# SLogger.net
KiCad netlist of a schematic drawn in EAGLE
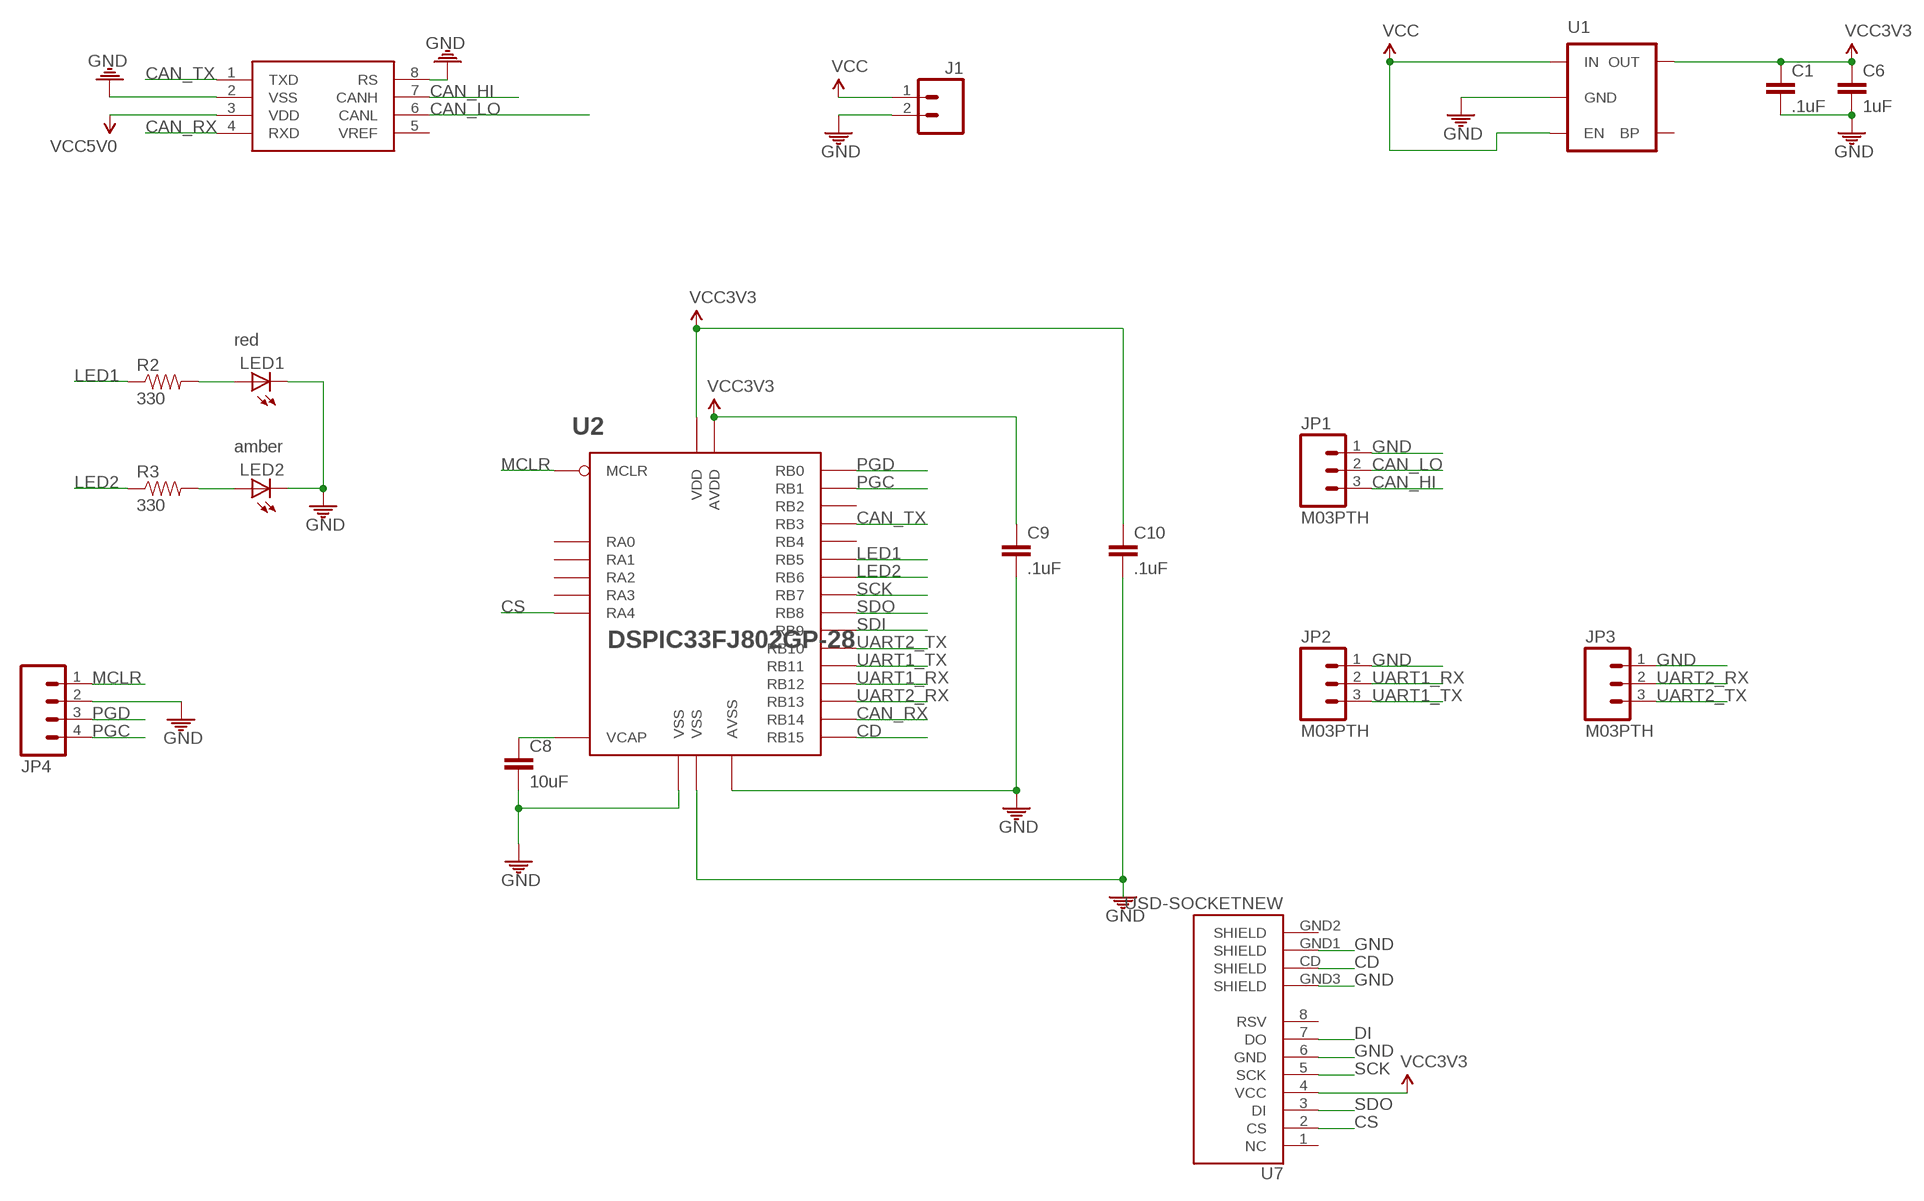
[diagram p0: schematic, sheet 1]

(export (version "E")
  (design (tool "Eeschema 10.0.6"))
  (components
    (comp (ref "C1")
      (value ".1uF")
      (footprint "eagle-import:0805")
      (libsource (lib "eagle-import") (part "CAP0805"))
    )
    (comp (ref "C6")
      (value "1uF")
      (footprint "eagle-import:0805")
      (libsource (lib "eagle-import") (part "CAP0805"))
    )
    (comp (ref "C8")
      (value "10uF")
      (footprint "eagle-import:0805")
      (libsource (lib "eagle-import") (part "CAP0805"))
    )
    (comp (ref "C9")
      (value ".1uF")
      (footprint "eagle-import:0805")
      (libsource (lib "eagle-import") (part "CAP0805"))
    )
    (comp (ref "C10")
      (value ".1uF")
      (footprint "eagle-import:0805")
      (libsource (lib "eagle-import") (part "CAP0805"))
    )
    (comp (ref "J1")
      (value "M02PTH")
      (footprint "eagle-import:1X02")
      (libsource (lib "eagle-import") (part "M02PTH"))
    )
    (comp (ref "JP1")
      (value "M03PTH")
      (footprint "eagle-import:1X03")
      (libsource (lib "eagle-import") (part "M03PTH"))
    )
    (comp (ref "JP2")
      (value "M03PTH")
      (footprint "eagle-import:1X03")
      (libsource (lib "eagle-import") (part "M03PTH"))
    )
    (comp (ref "JP3")
      (value "M03PTH")
      (footprint "eagle-import:1X03")
      (libsource (lib "eagle-import") (part "M03PTH"))
    )
    (comp (ref "JP4")
      (value "M04PTH")
      (footprint "eagle-import:1X04")
      (libsource (lib "eagle-import") (part "M04PTH"))
    )
    (comp (ref "LED1")
      (value "LED0805")
      (footprint "eagle-import:LED-0805")
      (fields (field (name "COLOR") "red"))
      (libsource (lib "eagle-import") (part "LED0805"))
    )
    (comp (ref "LED2")
      (value "LED0805")
      (footprint "eagle-import:LED-0805")
      (fields (field (name "COLOR") "amber"))
      (libsource (lib "eagle-import") (part "LED0805"))
    )
    (comp (ref "R2")
      (value "330")
      (footprint "eagle-import:0805")
      (libsource (lib "eagle-import") (part "RESISTOR0805-RES"))
    )
    (comp (ref "R3")
      (value "330")
      (footprint "eagle-import:0805")
      (libsource (lib "eagle-import") (part "RESISTOR0805-RES"))
    )
    (comp (ref "U1")
      (value "MIC52053.3V")
      (footprint "eagle-import:SOT23-5")
      (libsource (lib "eagle-import") (part "MIC52053.3V"))
    )
    (comp (ref "U2")
      (value "DSPIC33FJ802GP-28")
      (footprint "eagle-import:SOIC28-W")
      (libsource (lib "eagle-import") (part "DSPIC33FJ802GP-28"))
    )
    (comp (ref "U4")
      (value "MCP2551")
      (footprint "eagle-import:SO08")
      (libsource (lib "eagle-import") (part "MCP2551"))
    )
    (comp (ref "U7")
      (value "USD-SOCKETNEW")
      (footprint "eagle-import:MICRO-SD-SOCKET-PP")
      (libsource (lib "eagle-import") (part "USD-SOCKETNEW"))
    )
  )
  (nets
    (net (code "1") (name "/CAN_HI") (class "Default")
      (node (ref "JP1") (pin "3") (pinfunction "3_3") (pintype "passive"))
      (node (ref "U4") (pin "7") (pinfunction "CANH_7") (pintype "bidirectional"))
    )
    (net (code "2") (name "/CAN_LO") (class "Default")
      (node (ref "JP1") (pin "2") (pinfunction "2_2") (pintype "passive"))
      (node (ref "U4") (pin "6") (pinfunction "CANL_6") (pintype "bidirectional"))
    )
    (net (code "3") (name "/CAN_RX") (class "Default")
      (node (ref "U2") (pin "P$25") (pinfunction "RB14_P$25") (pintype "bidirectional"))
      (node (ref "U4") (pin "4") (pinfunction "RXD_4") (pintype "bidirectional"))
    )
    (net (code "4") (name "/CAN_TX") (class "Default")
      (node (ref "U2") (pin "P$7") (pinfunction "RB3_P$7") (pintype "bidirectional"))
      (node (ref "U4") (pin "1") (pinfunction "TXD_1") (pintype "bidirectional"))
    )
    (net (code "5") (name "/CD") (class "Default")
      (node (ref "U2") (pin "P$26") (pinfunction "RB15_P$26") (pintype "bidirectional"))
      (node (ref "U7") (pin "CD") (pinfunction "SHIELD_CD") (pintype "bidirectional"))
    )
    (net (code "6") (name "/CS") (class "Default")
      (node (ref "U2") (pin "P$12") (pinfunction "RA4_P$12") (pintype "bidirectional"))
      (node (ref "U7") (pin "2") (pinfunction "CS_2") (pintype "bidirectional"))
    )
    (net (code "7") (name "/DI") (class "Default")
      (node (ref "U7") (pin "7") (pinfunction "DO_7") (pintype "bidirectional"))
    )
    (net (code "8") (name "/LED1") (class "Default")
      (node (ref "R2") (pin "1") (pinfunction "1_1") (pintype "passive"))
      (node (ref "U2") (pin "P$14") (pinfunction "RB5_P$14") (pintype "bidirectional"))
    )
    (net (code "9") (name "/LED2") (class "Default")
      (node (ref "R3") (pin "1") (pinfunction "1_1") (pintype "passive"))
      (node (ref "U2") (pin "P$15") (pinfunction "RB6_P$15") (pintype "bidirectional"))
    )
    (net (code "10") (name "/MCLR") (class "Default")
      (node (ref "JP4") (pin "1") (pinfunction "1_1") (pintype "passive"))
      (node (ref "U2") (pin "P$1") (pinfunction "MCLR_P$1") (pintype "bidirectional"))
    )
    (net (code "11") (name "/PGC") (class "Default")
      (node (ref "JP4") (pin "4") (pinfunction "4_4") (pintype "passive"))
      (node (ref "U2") (pin "P$5") (pinfunction "RB1_P$5") (pintype "bidirectional"))
    )
    (net (code "12") (name "/PGD") (class "Default")
      (node (ref "JP4") (pin "3") (pinfunction "3_3") (pintype "passive"))
      (node (ref "U2") (pin "P$4") (pinfunction "RB0_P$4") (pintype "bidirectional"))
    )
    (net (code "13") (name "/SCK") (class "Default")
      (node (ref "U2") (pin "P$16") (pinfunction "RB7_P$16") (pintype "bidirectional"))
      (node (ref "U7") (pin "5") (pinfunction "SCK_5") (pintype "bidirectional"))
    )
    (net (code "14") (name "/SDI") (class "Default")
      (node (ref "U2") (pin "P$18") (pinfunction "RB9_P$18") (pintype "bidirectional"))
    )
    (net (code "15") (name "/SDO") (class "Default")
      (node (ref "U2") (pin "P$17") (pinfunction "RB8_P$17") (pintype "bidirectional"))
      (node (ref "U7") (pin "3") (pinfunction "DI_3") (pintype "bidirectional"))
    )
    (net (code "16") (name "/UART1_RX") (class "Default")
      (node (ref "JP2") (pin "2") (pinfunction "2_2") (pintype "passive"))
      (node (ref "U2") (pin "P$23") (pinfunction "RB12_P$23") (pintype "bidirectional"))
    )
    (net (code "17") (name "/UART1_TX") (class "Default")
      (node (ref "JP2") (pin "3") (pinfunction "3_3") (pintype "passive"))
      (node (ref "U2") (pin "P$22") (pinfunction "RB11_P$22") (pintype "bidirectional"))
    )
    (net (code "18") (name "/UART2_RX") (class "Default")
      (node (ref "JP3") (pin "2") (pinfunction "2_2") (pintype "passive"))
      (node (ref "U2") (pin "P$24") (pinfunction "RB13_P$24") (pintype "bidirectional"))
    )
    (net (code "19") (name "/UART2_TX") (class "Default")
      (node (ref "JP3") (pin "3") (pinfunction "3_3") (pintype "passive"))
      (node (ref "U2") (pin "P$21") (pinfunction "RB10_P$21") (pintype "bidirectional"))
    )
    (net (code "20") (name "GND") (class "Default")
      (node (ref "C1") (pin "2") (pinfunction "2_2") (pintype "passive"))
      (node (ref "C10") (pin "2") (pinfunction "2_2") (pintype "passive"))
      (node (ref "C6") (pin "2") (pinfunction "2_2") (pintype "passive"))
      (node (ref "C8") (pin "2") (pinfunction "2_2") (pintype "passive"))
      (node (ref "C9") (pin "2") (pinfunction "2_2") (pintype "passive"))
      (node (ref "J1") (pin "2") (pinfunction "1_2") (pintype "passive"))
      (node (ref "JP1") (pin "1") (pinfunction "1_1") (pintype "passive"))
      (node (ref "JP2") (pin "1") (pinfunction "1_1") (pintype "passive"))
      (node (ref "JP3") (pin "1") (pinfunction "1_1") (pintype "passive"))
      (node (ref "JP4") (pin "2") (pinfunction "2_2") (pintype "passive"))
      (node (ref "LED1") (pin "2") (pinfunction "C_2") (pintype "passive"))
      (node (ref "LED2") (pin "2") (pinfunction "C_2") (pintype "passive"))
      (node (ref "U1") (pin "2") (pinfunction "GND_2") (pintype "input"))
      (node (ref "U2") (pin "P$19") (pinfunction "VSS_P$19") (pintype "power_in"))
      (node (ref "U2") (pin "P$27") (pinfunction "AVSS_P$27") (pintype "input"))
      (node (ref "U2") (pin "P$8") (pinfunction "VSS_P$8") (pintype "power_in"))
      (node (ref "U4") (pin "2") (pinfunction "VSS_2") (pintype "bidirectional"))
      (node (ref "U4") (pin "8") (pinfunction "RS_8") (pintype "bidirectional"))
      (node (ref "U7") (pin "6") (pinfunction "GND_6") (pintype "bidirectional"))
      (node (ref "U7") (pin "GND1") (pinfunction "SHIELD_GND1") (pintype "bidirectional"))
      (node (ref "U7") (pin "GND3") (pinfunction "SHIELD_GND3") (pintype "bidirectional"))
    )
    (net (code "21") (name "Net-(LED1-A)") (class "Default")
      (node (ref "LED1") (pin "1") (pinfunction "A_1") (pintype "passive"))
      (node (ref "R2") (pin "2") (pinfunction "2_2") (pintype "passive"))
    )
    (net (code "22") (name "Net-(LED2-A)") (class "Default")
      (node (ref "LED2") (pin "1") (pinfunction "A_1") (pintype "passive"))
      (node (ref "R3") (pin "2") (pinfunction "2_2") (pintype "passive"))
    )
    (net (code "23") (name "Net-(U2-VCAP)") (class "Default")
      (node (ref "C8") (pin "1") (pinfunction "1_1") (pintype "passive"))
      (node (ref "U2") (pin "P$20") (pinfunction "VCAP_P$20") (pintype "input"))
    )
    (net (code "24") (name "VCC") (class "Default")
      (node (ref "J1") (pin "1") (pinfunction "2_1") (pintype "passive"))
      (node (ref "U1") (pin "1") (pinfunction "IN_1") (pintype "input"))
      (node (ref "U1") (pin "3") (pinfunction "EN_3") (pintype "input"))
    )
    (net (code "25") (name "VCC3V3") (class "Default")
      (node (ref "C1") (pin "1") (pinfunction "1_1") (pintype "passive"))
      (node (ref "C10") (pin "1") (pinfunction "1_1") (pintype "passive"))
      (node (ref "C6") (pin "1") (pinfunction "1_1") (pintype "passive"))
      (node (ref "C9") (pin "1") (pinfunction "1_1") (pintype "passive"))
      (node (ref "U1") (pin "5") (pinfunction "OUT_5") (pintype "passive"))
      (node (ref "U2") (pin "P$13") (pinfunction "VDD_P$13") (pintype "power_in"))
      (node (ref "U2") (pin "P$28") (pinfunction "AVDD_P$28") (pintype "input"))
      (node (ref "U7") (pin "4") (pinfunction "VCC_4") (pintype "bidirectional"))
    )
    (net (code "26") (name "VCC5V0") (class "Default")
      (node (ref "U4") (pin "3") (pinfunction "VDD_3") (pintype "bidirectional"))
    )
    (net (code "27") (name "unconnected-(U1-BP-Pad4)") (class "Default")
      (node (ref "U1") (pin "4") (pinfunction "BP_4") (pintype "input"))
    )
    (net (code "28") (name "unconnected-(U2-RA0-PadP$2)") (class "Default")
      (node (ref "U2") (pin "P$2") (pinfunction "RA0_P$2") (pintype "bidirectional"))
    )
    (net (code "29") (name "unconnected-(U2-RA1-PadP$3)") (class "Default")
      (node (ref "U2") (pin "P$3") (pinfunction "RA1_P$3") (pintype "bidirectional"))
    )
    (net (code "30") (name "unconnected-(U2-RA2-PadP$9)") (class "Default")
      (node (ref "U2") (pin "P$9") (pinfunction "RA2_P$9") (pintype "bidirectional"))
    )
    (net (code "31") (name "unconnected-(U2-RA3-PadP$10)") (class "Default")
      (node (ref "U2") (pin "P$10") (pinfunction "RA3_P$10") (pintype "bidirectional"))
    )
    (net (code "32") (name "unconnected-(U2-RB2-PadP$6)") (class "Default")
      (node (ref "U2") (pin "P$6") (pinfunction "RB2_P$6") (pintype "bidirectional"))
    )
    (net (code "33") (name "unconnected-(U2-RB4-PadP$11)") (class "Default")
      (node (ref "U2") (pin "P$11") (pinfunction "RB4_P$11") (pintype "bidirectional"))
    )
    (net (code "34") (name "unconnected-(U4-VREF-Pad5)") (class "Default")
      (node (ref "U4") (pin "5") (pinfunction "VREF_5") (pintype "bidirectional"))
    )
    (net (code "35") (name "unconnected-(U7-NC-Pad1)") (class "Default")
      (node (ref "U7") (pin "1") (pinfunction "NC_1") (pintype "bidirectional"))
    )
    (net (code "36") (name "unconnected-(U7-RSV-Pad8)") (class "Default")
      (node (ref "U7") (pin "8") (pinfunction "RSV_8") (pintype "bidirectional"))
    )
    (net (code "37") (name "unconnected-(U7-SHIELD-PadGND2)") (class "Default")
      (node (ref "U7") (pin "GND2") (pinfunction "SHIELD_GND2") (pintype "bidirectional"))
    )
  )
)
